# STLINK.net
KiCad netlist of a schematic drawn in Altium Designer
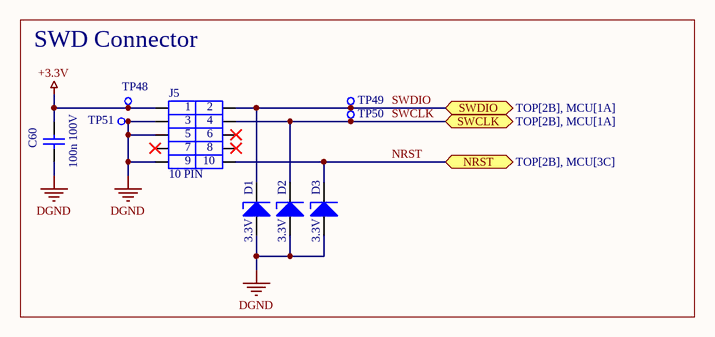
[diagram p0: STLINK.SchDoc]

(export (version "E")
  (design (tool "Eeschema 10.0.6"))
  (components
    (comp (ref "C60")
      (value "100n 100V")
      (footprint "FOOTPRINTS:CAPACITOR 0805")
      (description "Capacitor: ceramic; MLCC; 100nF; 100V; X7R; ±10%; SMD; 0805")
      (fields
        (field (name "MANUFACTURER") "YAGEO")
        (field (name "MANUFACTURER PART NUMBER") "CC0805KKX7R0BB104")
      )
      (libsource (lib "SYMBOLS") (part "Capacitor 100n 100V 10% X7R 0805"))
    )
    (comp (ref "D1")
      (value "3.3V")
      (footprint "FOOTPRINTS:DIODE SOD523F")
      (description "Diode: TVS; 134W; 5V; 11.2A; unidirectional; SOD523F; reel,tape")
      (fields
        (field (name "MANUFACTURER") "DIOTEC SEMICONDUCTOR")
        (field (name "MANUFACTURER PART NUMBER") "ESD5Z3V3")
      )
      (libsource (lib "SYMBOLS") (part "Diode TVS 3.3V Unidirectional ESD5Z3V3"))
    )
    (comp (ref "D2")
      (value "3.3V")
      (footprint "FOOTPRINTS:DIODE SOD523F")
      (description "Diode: TVS; 134W; 5V; 11.2A; unidirectional; SOD523F; reel,tape")
      (fields
        (field (name "MANUFACTURER") "DIOTEC SEMICONDUCTOR")
        (field (name "MANUFACTURER PART NUMBER") "ESD5Z3V3")
      )
      (libsource (lib "SYMBOLS") (part "Diode TVS 3.3V Unidirectional ESD5Z3V3"))
    )
    (comp (ref "D3")
      (value "3.3V")
      (footprint "FOOTPRINTS:DIODE SOD523F")
      (description "Diode: TVS; 134W; 5V; 11.2A; unidirectional; SOD523F; reel,tape")
      (fields
        (field (name "MANUFACTURER") "DIOTEC SEMICONDUCTOR")
        (field (name "MANUFACTURER PART NUMBER") "ESD5Z3V3")
      )
      (libsource (lib "SYMBOLS") (part "Diode TVS 3.3V Unidirectional ESD5Z3V3"))
    )
    (comp (ref "J5")
      (value "10 PIN")
      (footprint "FOOTPRINTS:MECHANICAL PINHEADER 2x5P 1.27MM MALE")
      (description "Pin header; pin strips; male; PIN: 10; straight; 1.27mm; THT; 2x5")
      (fields
        (field (name "MANUFACTURER") "CONNFLY")
        (field (name "MANUFACTURER PART NUMBER") "DS1031-06-2*5P8BV41-3A")
      )
      (libsource (lib "SYMBOLS") (part "Mechanical Pinheader Male 2x5pin P=1.27mm THT"))
    )
    (comp (ref "TP48")
      (value "1mm")
      (footprint "FOOTPRINTS:TEST POINT 1MM")
      (description "Tesp Point 1mm")
      (libsource (lib "SYMBOLS") (part "Mechanical Test Point 1mm"))
    )
    (comp (ref "TP49")
      (value "1mm")
      (footprint "FOOTPRINTS:TEST POINT 1MM")
      (description "Tesp Point 1mm")
      (libsource (lib "SYMBOLS") (part "Mechanical Test Point 1mm"))
    )
    (comp (ref "TP50")
      (value "1mm")
      (footprint "FOOTPRINTS:TEST POINT 1MM")
      (description "Tesp Point 1mm")
      (libsource (lib "SYMBOLS") (part "Mechanical Test Point 1mm"))
    )
    (comp (ref "TP51")
      (value "1mm")
      (footprint "FOOTPRINTS:TEST POINT 1MM")
      (description "Tesp Point 1mm")
      (libsource (lib "SYMBOLS") (part "Mechanical Test Point 1mm"))
    )
  )
  (nets
    (net (code "1") (name "+3.3V") (class "Default")
      (node (ref "C60") (pin "2") (pinfunction "2_2") (pintype "passive"))
      (node (ref "J5") (pin "1") (pinfunction "1_1") (pintype "passive"))
      (node (ref "TP48") (pin "1") (pinfunction "1_1") (pintype "passive"))
    )
    (net (code "2") (name "/NRST") (class "Default")
      (node (ref "D3") (pin "2") (pinfunction "2_2") (pintype "passive"))
      (node (ref "J5") (pin "10") (pinfunction "10_10") (pintype "passive"))
    )
    (net (code "3") (name "/SWCLK") (class "Default")
      (node (ref "D2") (pin "2") (pinfunction "2_2") (pintype "passive"))
      (node (ref "J5") (pin "4") (pinfunction "4_4") (pintype "passive"))
      (node (ref "TP50") (pin "1") (pinfunction "1_1") (pintype "passive"))
    )
    (net (code "4") (name "/SWDIO") (class "Default")
      (node (ref "D1") (pin "2") (pinfunction "2_2") (pintype "passive"))
      (node (ref "J5") (pin "2") (pinfunction "2_2") (pintype "passive"))
      (node (ref "TP49") (pin "1") (pinfunction "1_1") (pintype "passive"))
    )
    (net (code "5") (name "DGND") (class "Default")
      (node (ref "C60") (pin "1") (pinfunction "1_1") (pintype "passive"))
      (node (ref "D1") (pin "1") (pinfunction "1_1") (pintype "passive"))
      (node (ref "D2") (pin "1") (pinfunction "1_1") (pintype "passive"))
      (node (ref "D3") (pin "1") (pinfunction "1_1") (pintype "passive"))
      (node (ref "J5") (pin "3") (pinfunction "3_3") (pintype "passive"))
      (node (ref "J5") (pin "5") (pinfunction "5_5") (pintype "passive"))
      (node (ref "J5") (pin "9") (pinfunction "9_9") (pintype "passive"))
      (node (ref "TP51") (pin "1") (pinfunction "1_1") (pintype "passive"))
    )
    (net (code "6") (name "unconnected-(J5-Pad6)") (class "Default")
      (node (ref "J5") (pin "6") (pinfunction "6_6") (pintype "passive+no_connect"))
    )
    (net (code "7") (name "unconnected-(J5-Pad7)") (class "Default")
      (node (ref "J5") (pin "7") (pinfunction "7_7") (pintype "passive+no_connect"))
    )
    (net (code "8") (name "unconnected-(J5-Pad8)") (class "Default")
      (node (ref "J5") (pin "8") (pinfunction "8_8") (pintype "passive+no_connect"))
    )
  )
)
